# shield.net
KiCad netlist of a schematic drawn in EAGLE
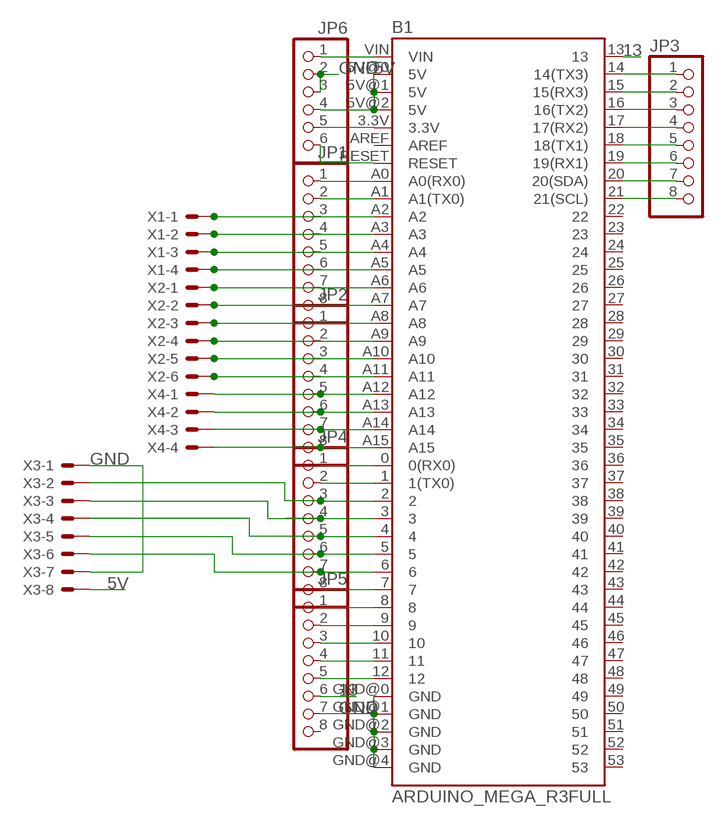
[diagram p0: schematic, sheet 1]

(export (version "E")
  (design (tool "Eeschema 10.0.6"))
  (components
    (comp (ref "B1")
      (value "ARDUINO_MEGA_R3FULL")
      (footprint "eagle-import:ARDUINO_MEGA")
      (libsource (lib "eagle-import") (part "ARDUINO_MEGA_R3FULL"))
    )
    (comp (ref "JP1")
      (value "PINHD-1X8")
      (footprint "eagle-import:1X08")
      (libsource (lib "eagle-import") (part "PINHD-1X8"))
    )
    (comp (ref "JP2")
      (value "PINHD-1X8")
      (footprint "eagle-import:1X08")
      (libsource (lib "eagle-import") (part "PINHD-1X8"))
    )
    (comp (ref "JP3")
      (value "PINHD-1X8")
      (footprint "eagle-import:1X08")
      (libsource (lib "eagle-import") (part "PINHD-1X8"))
    )
    (comp (ref "JP4")
      (value "PINHD-1X8")
      (footprint "eagle-import:1X08")
      (libsource (lib "eagle-import") (part "PINHD-1X8"))
    )
    (comp (ref "JP5")
      (value "PINHD-1X8")
      (footprint "eagle-import:1X08")
      (libsource (lib "eagle-import") (part "PINHD-1X8"))
    )
    (comp (ref "JP6")
      (value "PINHD-1X6")
      (footprint "eagle-import:1X06")
      (libsource (lib "eagle-import") (part "PINHD-1X6"))
    )
    (comp (ref "X1")
      (value "JST-XH-04-PIN-LONG-PAD")
      (footprint "eagle-import:JST-XH-04-PACKAGE-LONG-PAD")
      (libsource (lib "eagle-import") (part "JST-XH-04-PIN-LONG-PAD"))
    )
    (comp (ref "X2")
      (value "JST-XH-06-PIN-LONG-PAD")
      (footprint "eagle-import:JST-XH-06-PACKAGE-LONG-PAD")
      (libsource (lib "eagle-import") (part "JST-XH-06-PIN-LONG-PAD"))
    )
    (comp (ref "X3")
      (value "JST-XH-08-PIN-LONG-PAD")
      (footprint "eagle-import:JST-XH-08-PACKAGE-LONG-PAD")
      (libsource (lib "eagle-import") (part "JST-XH-08-PIN-LONG-PAD"))
    )
    (comp (ref "X4")
      (value "JST-XH-04-PIN-LONG-PAD")
      (footprint "eagle-import:JST-XH-04-PACKAGE-LONG-PAD")
      (libsource (lib "eagle-import") (part "JST-XH-04-PIN-LONG-PAD"))
    )
  )
  (nets
    (net (code "1") (name "/5V") (class "Default")
      (node (ref "B1") (pin "5V@0") (pinfunction "5V_5V@0") (pintype "bidirectional"))
      (node (ref "B1") (pin "5V@1") (pinfunction "5V_5V@1") (pintype "bidirectional"))
      (node (ref "B1") (pin "5V@2") (pinfunction "5V_5V@2") (pintype "bidirectional"))
      (node (ref "JP6") (pin "4") (pinfunction "4_4") (pintype "passive"))
      (node (ref "X3") (pin "8") (pinfunction "S_8") (pintype "passive"))
    )
    (net (code "2") (name "/13") (class "Default")
      (node (ref "B1") (pin "13") (pinfunction "13_13") (pintype "bidirectional"))
      (node (ref "JP5") (pin "6") (pinfunction "6_6") (pintype "passive"))
    )
    (net (code "3") (name "/GND") (class "Default")
      (node (ref "B1") (pin "GND@0") (pinfunction "GND_GND@0") (pintype "bidirectional"))
      (node (ref "B1") (pin "GND@1") (pinfunction "GND_GND@1") (pintype "bidirectional"))
      (node (ref "B1") (pin "GND@2") (pinfunction "GND_GND@2") (pintype "bidirectional"))
      (node (ref "B1") (pin "GND@3") (pinfunction "GND_GND@3") (pintype "bidirectional"))
      (node (ref "B1") (pin "GND@4") (pinfunction "GND_GND@4") (pintype "bidirectional"))
      (node (ref "JP5") (pin "7") (pinfunction "7_7") (pintype "passive"))
      (node (ref "JP6") (pin "2") (pinfunction "2_2") (pintype "passive"))
      (node (ref "JP6") (pin "3") (pinfunction "3_3") (pintype "passive"))
      (node (ref "X3") (pin "1") (pinfunction "S_1") (pintype "passive"))
      (node (ref "X3") (pin "7") (pinfunction "S_7") (pintype "passive"))
    )
    (net (code "4") (name "Net-(B1-0(RX0))") (class "Default")
      (node (ref "B1") (pin "0") (pinfunction "0(RX0)_0") (pintype "bidirectional"))
      (node (ref "JP4") (pin "1") (pinfunction "1_1") (pintype "passive"))
    )
    (net (code "5") (name "Net-(B1-1(TX0))") (class "Default")
      (node (ref "B1") (pin "1") (pinfunction "1(TX0)_1") (pintype "bidirectional"))
      (node (ref "JP4") (pin "2") (pinfunction "2_2") (pintype "passive"))
    )
    (net (code "6") (name "Net-(B1-14(TX3))") (class "Default")
      (node (ref "B1") (pin "14") (pinfunction "14(TX3)_14") (pintype "bidirectional"))
      (node (ref "JP3") (pin "1") (pinfunction "1_1") (pintype "passive"))
    )
    (net (code "7") (name "Net-(B1-15(RX3))") (class "Default")
      (node (ref "B1") (pin "15") (pinfunction "15(RX3)_15") (pintype "bidirectional"))
      (node (ref "JP3") (pin "2") (pinfunction "2_2") (pintype "passive"))
    )
    (net (code "8") (name "Net-(B1-16(TX2))") (class "Default")
      (node (ref "B1") (pin "16") (pinfunction "16(TX2)_16") (pintype "bidirectional"))
      (node (ref "JP3") (pin "3") (pinfunction "3_3") (pintype "passive"))
    )
    (net (code "9") (name "Net-(B1-17(RX2))") (class "Default")
      (node (ref "B1") (pin "17") (pinfunction "17(RX2)_17") (pintype "bidirectional"))
      (node (ref "JP3") (pin "4") (pinfunction "4_4") (pintype "passive"))
    )
    (net (code "10") (name "Net-(B1-18(TX1))") (class "Default")
      (node (ref "B1") (pin "18") (pinfunction "18(TX1)_18") (pintype "bidirectional"))
      (node (ref "JP3") (pin "5") (pinfunction "5_5") (pintype "passive"))
    )
    (net (code "11") (name "Net-(B1-19(RX1))") (class "Default")
      (node (ref "B1") (pin "19") (pinfunction "19(RX1)_19") (pintype "bidirectional"))
      (node (ref "JP3") (pin "6") (pinfunction "6_6") (pintype "passive"))
    )
    (net (code "12") (name "Net-(B1-20(SDA))") (class "Default")
      (node (ref "B1") (pin "20") (pinfunction "20(SDA)_20") (pintype "bidirectional"))
      (node (ref "JP3") (pin "7") (pinfunction "7_7") (pintype "passive"))
    )
    (net (code "13") (name "Net-(B1-21(SCL))") (class "Default")
      (node (ref "B1") (pin "21") (pinfunction "21(SCL)_21") (pintype "bidirectional"))
      (node (ref "JP3") (pin "8") (pinfunction "8_8") (pintype "passive"))
    )
    (net (code "14") (name "Net-(B1-A0(RX0))") (class "Default")
      (node (ref "B1") (pin "A0") (pinfunction "A0(RX0)_A0") (pintype "bidirectional"))
      (node (ref "JP1") (pin "1") (pinfunction "1_1") (pintype "passive"))
    )
    (net (code "15") (name "Net-(B1-A1(TX0))") (class "Default")
      (node (ref "B1") (pin "A1") (pinfunction "A1(TX0)_A1") (pintype "bidirectional"))
      (node (ref "JP1") (pin "2") (pinfunction "2_2") (pintype "passive"))
    )
    (net (code "16") (name "Net-(B1-Pad3.3V)") (class "Default")
      (node (ref "B1") (pin "3.3V") (pinfunction "3.3V_3.3V") (pintype "bidirectional"))
      (node (ref "JP6") (pin "5") (pinfunction "5_5") (pintype "passive"))
    )
    (net (code "17") (name "Net-(B1-Pad7)") (class "Default")
      (node (ref "B1") (pin "7") (pinfunction "7_7") (pintype "bidirectional"))
      (node (ref "JP4") (pin "8") (pinfunction "8_8") (pintype "passive"))
    )
    (net (code "18") (name "Net-(B1-Pad8)") (class "Default")
      (node (ref "B1") (pin "8") (pinfunction "8_8") (pintype "bidirectional"))
      (node (ref "JP5") (pin "1") (pinfunction "1_1") (pintype "passive"))
    )
    (net (code "19") (name "Net-(B1-Pad9)") (class "Default")
      (node (ref "B1") (pin "9") (pinfunction "9_9") (pintype "bidirectional"))
      (node (ref "JP5") (pin "2") (pinfunction "2_2") (pintype "passive"))
    )
    (net (code "20") (name "Net-(B1-Pad10)") (class "Default")
      (node (ref "B1") (pin "10") (pinfunction "10_10") (pintype "bidirectional"))
      (node (ref "JP5") (pin "3") (pinfunction "3_3") (pintype "passive"))
    )
    (net (code "21") (name "Net-(B1-Pad11)") (class "Default")
      (node (ref "B1") (pin "11") (pinfunction "11_11") (pintype "bidirectional"))
      (node (ref "JP5") (pin "4") (pinfunction "4_4") (pintype "passive"))
    )
    (net (code "22") (name "Net-(B1-Pad12)") (class "Default")
      (node (ref "B1") (pin "12") (pinfunction "12_12") (pintype "bidirectional"))
      (node (ref "JP5") (pin "5") (pinfunction "5_5") (pintype "passive"))
    )
    (net (code "23") (name "Net-(B1-PadRESET)") (class "Default")
      (node (ref "B1") (pin "RESET") (pinfunction "RESET_RESET") (pintype "bidirectional"))
      (node (ref "JP6") (pin "6") (pinfunction "6_6") (pintype "passive"))
    )
    (net (code "24") (name "Net-(B1-PadVIN)") (class "Default")
      (node (ref "B1") (pin "VIN") (pinfunction "VIN_VIN") (pintype "bidirectional"))
      (node (ref "JP6") (pin "1") (pinfunction "1_1") (pintype "passive"))
    )
    (net (code "25") (name "Net-(X1A-S)") (class "Default")
      (node (ref "B1") (pin "A2") (pinfunction "A2_A2") (pintype "bidirectional"))
      (node (ref "JP1") (pin "3") (pinfunction "3_3") (pintype "passive"))
      (node (ref "X1") (pin "1") (pinfunction "S_1") (pintype "passive"))
    )
    (net (code "26") (name "Net-(X1B-S)") (class "Default")
      (node (ref "B1") (pin "A3") (pinfunction "A3_A3") (pintype "bidirectional"))
      (node (ref "JP1") (pin "4") (pinfunction "4_4") (pintype "passive"))
      (node (ref "X1") (pin "2") (pinfunction "S_2") (pintype "passive"))
    )
    (net (code "27") (name "Net-(X1C-S)") (class "Default")
      (node (ref "B1") (pin "A4") (pinfunction "A4_A4") (pintype "bidirectional"))
      (node (ref "JP1") (pin "5") (pinfunction "5_5") (pintype "passive"))
      (node (ref "X1") (pin "3") (pinfunction "S_3") (pintype "passive"))
    )
    (net (code "28") (name "Net-(X1D-S)") (class "Default")
      (node (ref "B1") (pin "A5") (pinfunction "A5_A5") (pintype "bidirectional"))
      (node (ref "JP1") (pin "6") (pinfunction "6_6") (pintype "passive"))
      (node (ref "X1") (pin "4") (pinfunction "S_4") (pintype "passive"))
    )
    (net (code "29") (name "Net-(X2A-S)") (class "Default")
      (node (ref "B1") (pin "A6") (pinfunction "A6_A6") (pintype "bidirectional"))
      (node (ref "JP1") (pin "7") (pinfunction "7_7") (pintype "passive"))
      (node (ref "X2") (pin "1") (pinfunction "S_1") (pintype "passive"))
    )
    (net (code "30") (name "Net-(X2B-S)") (class "Default")
      (node (ref "B1") (pin "A7") (pinfunction "A7_A7") (pintype "bidirectional"))
      (node (ref "JP1") (pin "8") (pinfunction "8_8") (pintype "passive"))
      (node (ref "X2") (pin "2") (pinfunction "S_2") (pintype "passive"))
    )
    (net (code "31") (name "Net-(X2C-S)") (class "Default")
      (node (ref "B1") (pin "A8") (pinfunction "A8_A8") (pintype "bidirectional"))
      (node (ref "JP2") (pin "1") (pinfunction "1_1") (pintype "passive"))
      (node (ref "X2") (pin "3") (pinfunction "S_3") (pintype "passive"))
    )
    (net (code "32") (name "Net-(X2D-S)") (class "Default")
      (node (ref "B1") (pin "A9") (pinfunction "A9_A9") (pintype "bidirectional"))
      (node (ref "JP2") (pin "2") (pinfunction "2_2") (pintype "passive"))
      (node (ref "X2") (pin "4") (pinfunction "S_4") (pintype "passive"))
    )
    (net (code "33") (name "Net-(X2E-S)") (class "Default")
      (node (ref "B1") (pin "A10") (pinfunction "A10_A10") (pintype "bidirectional"))
      (node (ref "JP2") (pin "3") (pinfunction "3_3") (pintype "passive"))
      (node (ref "X2") (pin "5") (pinfunction "S_5") (pintype "passive"))
    )
    (net (code "34") (name "Net-(X2F-S)") (class "Default")
      (node (ref "B1") (pin "A11") (pinfunction "A11_A11") (pintype "bidirectional"))
      (node (ref "JP2") (pin "4") (pinfunction "4_4") (pintype "passive"))
      (node (ref "X2") (pin "6") (pinfunction "S_6") (pintype "passive"))
    )
    (net (code "35") (name "Net-(X3B-S)") (class "Default")
      (node (ref "B1") (pin "2") (pinfunction "2_2") (pintype "bidirectional"))
      (node (ref "JP4") (pin "3") (pinfunction "3_3") (pintype "passive"))
      (node (ref "X3") (pin "2") (pinfunction "S_2") (pintype "passive"))
    )
    (net (code "36") (name "Net-(X3C-S)") (class "Default")
      (node (ref "B1") (pin "3") (pinfunction "3_3") (pintype "bidirectional"))
      (node (ref "JP4") (pin "4") (pinfunction "4_4") (pintype "passive"))
      (node (ref "X3") (pin "3") (pinfunction "S_3") (pintype "passive"))
    )
    (net (code "37") (name "Net-(X3D-S)") (class "Default")
      (node (ref "B1") (pin "4") (pinfunction "4_4") (pintype "bidirectional"))
      (node (ref "JP4") (pin "5") (pinfunction "5_5") (pintype "passive"))
      (node (ref "X3") (pin "4") (pinfunction "S_4") (pintype "passive"))
    )
    (net (code "38") (name "Net-(X3E-S)") (class "Default")
      (node (ref "B1") (pin "5") (pinfunction "5_5") (pintype "bidirectional"))
      (node (ref "JP4") (pin "6") (pinfunction "6_6") (pintype "passive"))
      (node (ref "X3") (pin "5") (pinfunction "S_5") (pintype "passive"))
    )
    (net (code "39") (name "Net-(X3F-S)") (class "Default")
      (node (ref "B1") (pin "6") (pinfunction "6_6") (pintype "bidirectional"))
      (node (ref "JP4") (pin "7") (pinfunction "7_7") (pintype "passive"))
      (node (ref "X3") (pin "6") (pinfunction "S_6") (pintype "passive"))
    )
    (net (code "40") (name "Net-(X4A-S)") (class "Default")
      (node (ref "B1") (pin "A12") (pinfunction "A12_A12") (pintype "bidirectional"))
      (node (ref "JP2") (pin "5") (pinfunction "5_5") (pintype "passive"))
      (node (ref "X4") (pin "1") (pinfunction "S_1") (pintype "passive"))
    )
    (net (code "41") (name "Net-(X4B-S)") (class "Default")
      (node (ref "B1") (pin "A13") (pinfunction "A13_A13") (pintype "bidirectional"))
      (node (ref "JP2") (pin "6") (pinfunction "6_6") (pintype "passive"))
      (node (ref "X4") (pin "2") (pinfunction "S_2") (pintype "passive"))
    )
    (net (code "42") (name "Net-(X4C-S)") (class "Default")
      (node (ref "B1") (pin "A14") (pinfunction "A14_A14") (pintype "bidirectional"))
      (node (ref "JP2") (pin "7") (pinfunction "7_7") (pintype "passive"))
      (node (ref "X4") (pin "3") (pinfunction "S_3") (pintype "passive"))
    )
    (net (code "43") (name "Net-(X4D-S)") (class "Default")
      (node (ref "B1") (pin "A15") (pinfunction "A15_A15") (pintype "bidirectional"))
      (node (ref "JP2") (pin "8") (pinfunction "8_8") (pintype "passive"))
      (node (ref "X4") (pin "4") (pinfunction "S_4") (pintype "passive"))
    )
    (net (code "44") (name "unconnected-(B1-Pad22)") (class "Default")
      (node (ref "B1") (pin "22") (pinfunction "22_22") (pintype "bidirectional"))
    )
    (net (code "45") (name "unconnected-(B1-Pad23)") (class "Default")
      (node (ref "B1") (pin "23") (pinfunction "23_23") (pintype "bidirectional"))
    )
    (net (code "46") (name "unconnected-(B1-Pad24)") (class "Default")
      (node (ref "B1") (pin "24") (pinfunction "24_24") (pintype "bidirectional"))
    )
    (net (code "47") (name "unconnected-(B1-Pad25)") (class "Default")
      (node (ref "B1") (pin "25") (pinfunction "25_25") (pintype "bidirectional"))
    )
    (net (code "48") (name "unconnected-(B1-Pad26)") (class "Default")
      (node (ref "B1") (pin "26") (pinfunction "26_26") (pintype "bidirectional"))
    )
    (net (code "49") (name "unconnected-(B1-Pad27)") (class "Default")
      (node (ref "B1") (pin "27") (pinfunction "27_27") (pintype "bidirectional"))
    )
    (net (code "50") (name "unconnected-(B1-Pad28)") (class "Default")
      (node (ref "B1") (pin "28") (pinfunction "28_28") (pintype "bidirectional"))
    )
    (net (code "51") (name "unconnected-(B1-Pad29)") (class "Default")
      (node (ref "B1") (pin "29") (pinfunction "29_29") (pintype "bidirectional"))
    )
    (net (code "52") (name "unconnected-(B1-Pad30)") (class "Default")
      (node (ref "B1") (pin "30") (pinfunction "30_30") (pintype "bidirectional"))
    )
    (net (code "53") (name "unconnected-(B1-Pad31)") (class "Default")
      (node (ref "B1") (pin "31") (pinfunction "31_31") (pintype "bidirectional"))
    )
    (net (code "54") (name "unconnected-(B1-Pad32)") (class "Default")
      (node (ref "B1") (pin "32") (pinfunction "32_32") (pintype "bidirectional"))
    )
    (net (code "55") (name "unconnected-(B1-Pad33)") (class "Default")
      (node (ref "B1") (pin "33") (pinfunction "33_33") (pintype "bidirectional"))
    )
    (net (code "56") (name "unconnected-(B1-Pad34)") (class "Default")
      (node (ref "B1") (pin "34") (pinfunction "34_34") (pintype "bidirectional"))
    )
    (net (code "57") (name "unconnected-(B1-Pad35)") (class "Default")
      (node (ref "B1") (pin "35") (pinfunction "35_35") (pintype "bidirectional"))
    )
    (net (code "58") (name "unconnected-(B1-Pad36)") (class "Default")
      (node (ref "B1") (pin "36") (pinfunction "36_36") (pintype "bidirectional"))
    )
    (net (code "59") (name "unconnected-(B1-Pad37)") (class "Default")
      (node (ref "B1") (pin "37") (pinfunction "37_37") (pintype "bidirectional"))
    )
    (net (code "60") (name "unconnected-(B1-Pad38)") (class "Default")
      (node (ref "B1") (pin "38") (pinfunction "38_38") (pintype "bidirectional"))
    )
    (net (code "61") (name "unconnected-(B1-Pad39)") (class "Default")
      (node (ref "B1") (pin "39") (pinfunction "39_39") (pintype "bidirectional"))
    )
    (net (code "62") (name "unconnected-(B1-Pad40)") (class "Default")
      (node (ref "B1") (pin "40") (pinfunction "40_40") (pintype "bidirectional"))
    )
    (net (code "63") (name "unconnected-(B1-Pad41)") (class "Default")
      (node (ref "B1") (pin "41") (pinfunction "41_41") (pintype "bidirectional"))
    )
    (net (code "64") (name "unconnected-(B1-Pad42)") (class "Default")
      (node (ref "B1") (pin "42") (pinfunction "42_42") (pintype "bidirectional"))
    )
    (net (code "65") (name "unconnected-(B1-Pad43)") (class "Default")
      (node (ref "B1") (pin "43") (pinfunction "43_43") (pintype "bidirectional"))
    )
    (net (code "66") (name "unconnected-(B1-Pad44)") (class "Default")
      (node (ref "B1") (pin "44") (pinfunction "44_44") (pintype "bidirectional"))
    )
    (net (code "67") (name "unconnected-(B1-Pad45)") (class "Default")
      (node (ref "B1") (pin "45") (pinfunction "45_45") (pintype "bidirectional"))
    )
    (net (code "68") (name "unconnected-(B1-Pad46)") (class "Default")
      (node (ref "B1") (pin "46") (pinfunction "46_46") (pintype "bidirectional"))
    )
    (net (code "69") (name "unconnected-(B1-Pad47)") (class "Default")
      (node (ref "B1") (pin "47") (pinfunction "47_47") (pintype "bidirectional"))
    )
    (net (code "70") (name "unconnected-(B1-Pad48)") (class "Default")
      (node (ref "B1") (pin "48") (pinfunction "48_48") (pintype "bidirectional"))
    )
    (net (code "71") (name "unconnected-(B1-Pad49)") (class "Default")
      (node (ref "B1") (pin "49") (pinfunction "49_49") (pintype "bidirectional"))
    )
    (net (code "72") (name "unconnected-(B1-Pad50)") (class "Default")
      (node (ref "B1") (pin "50") (pinfunction "50_50") (pintype "bidirectional"))
    )
    (net (code "73") (name "unconnected-(B1-Pad51)") (class "Default")
      (node (ref "B1") (pin "51") (pinfunction "51_51") (pintype "bidirectional"))
    )
    (net (code "74") (name "unconnected-(B1-Pad52)") (class "Default")
      (node (ref "B1") (pin "52") (pinfunction "52_52") (pintype "bidirectional"))
    )
    (net (code "75") (name "unconnected-(B1-Pad53)") (class "Default")
      (node (ref "B1") (pin "53") (pinfunction "53_53") (pintype "bidirectional"))
    )
    (net (code "76") (name "unconnected-(B1-PadAREF)") (class "Default")
      (node (ref "B1") (pin "AREF") (pinfunction "AREF_AREF") (pintype "bidirectional"))
    )
    (net (code "77") (name "unconnected-(JP5-Pad8)") (class "Default")
      (node (ref "JP5") (pin "8") (pinfunction "8_8") (pintype "passive"))
    )
  )
)
